# MCU_STM32H743BI.net
KiCad netlist of a schematic drawn in Altium Designer
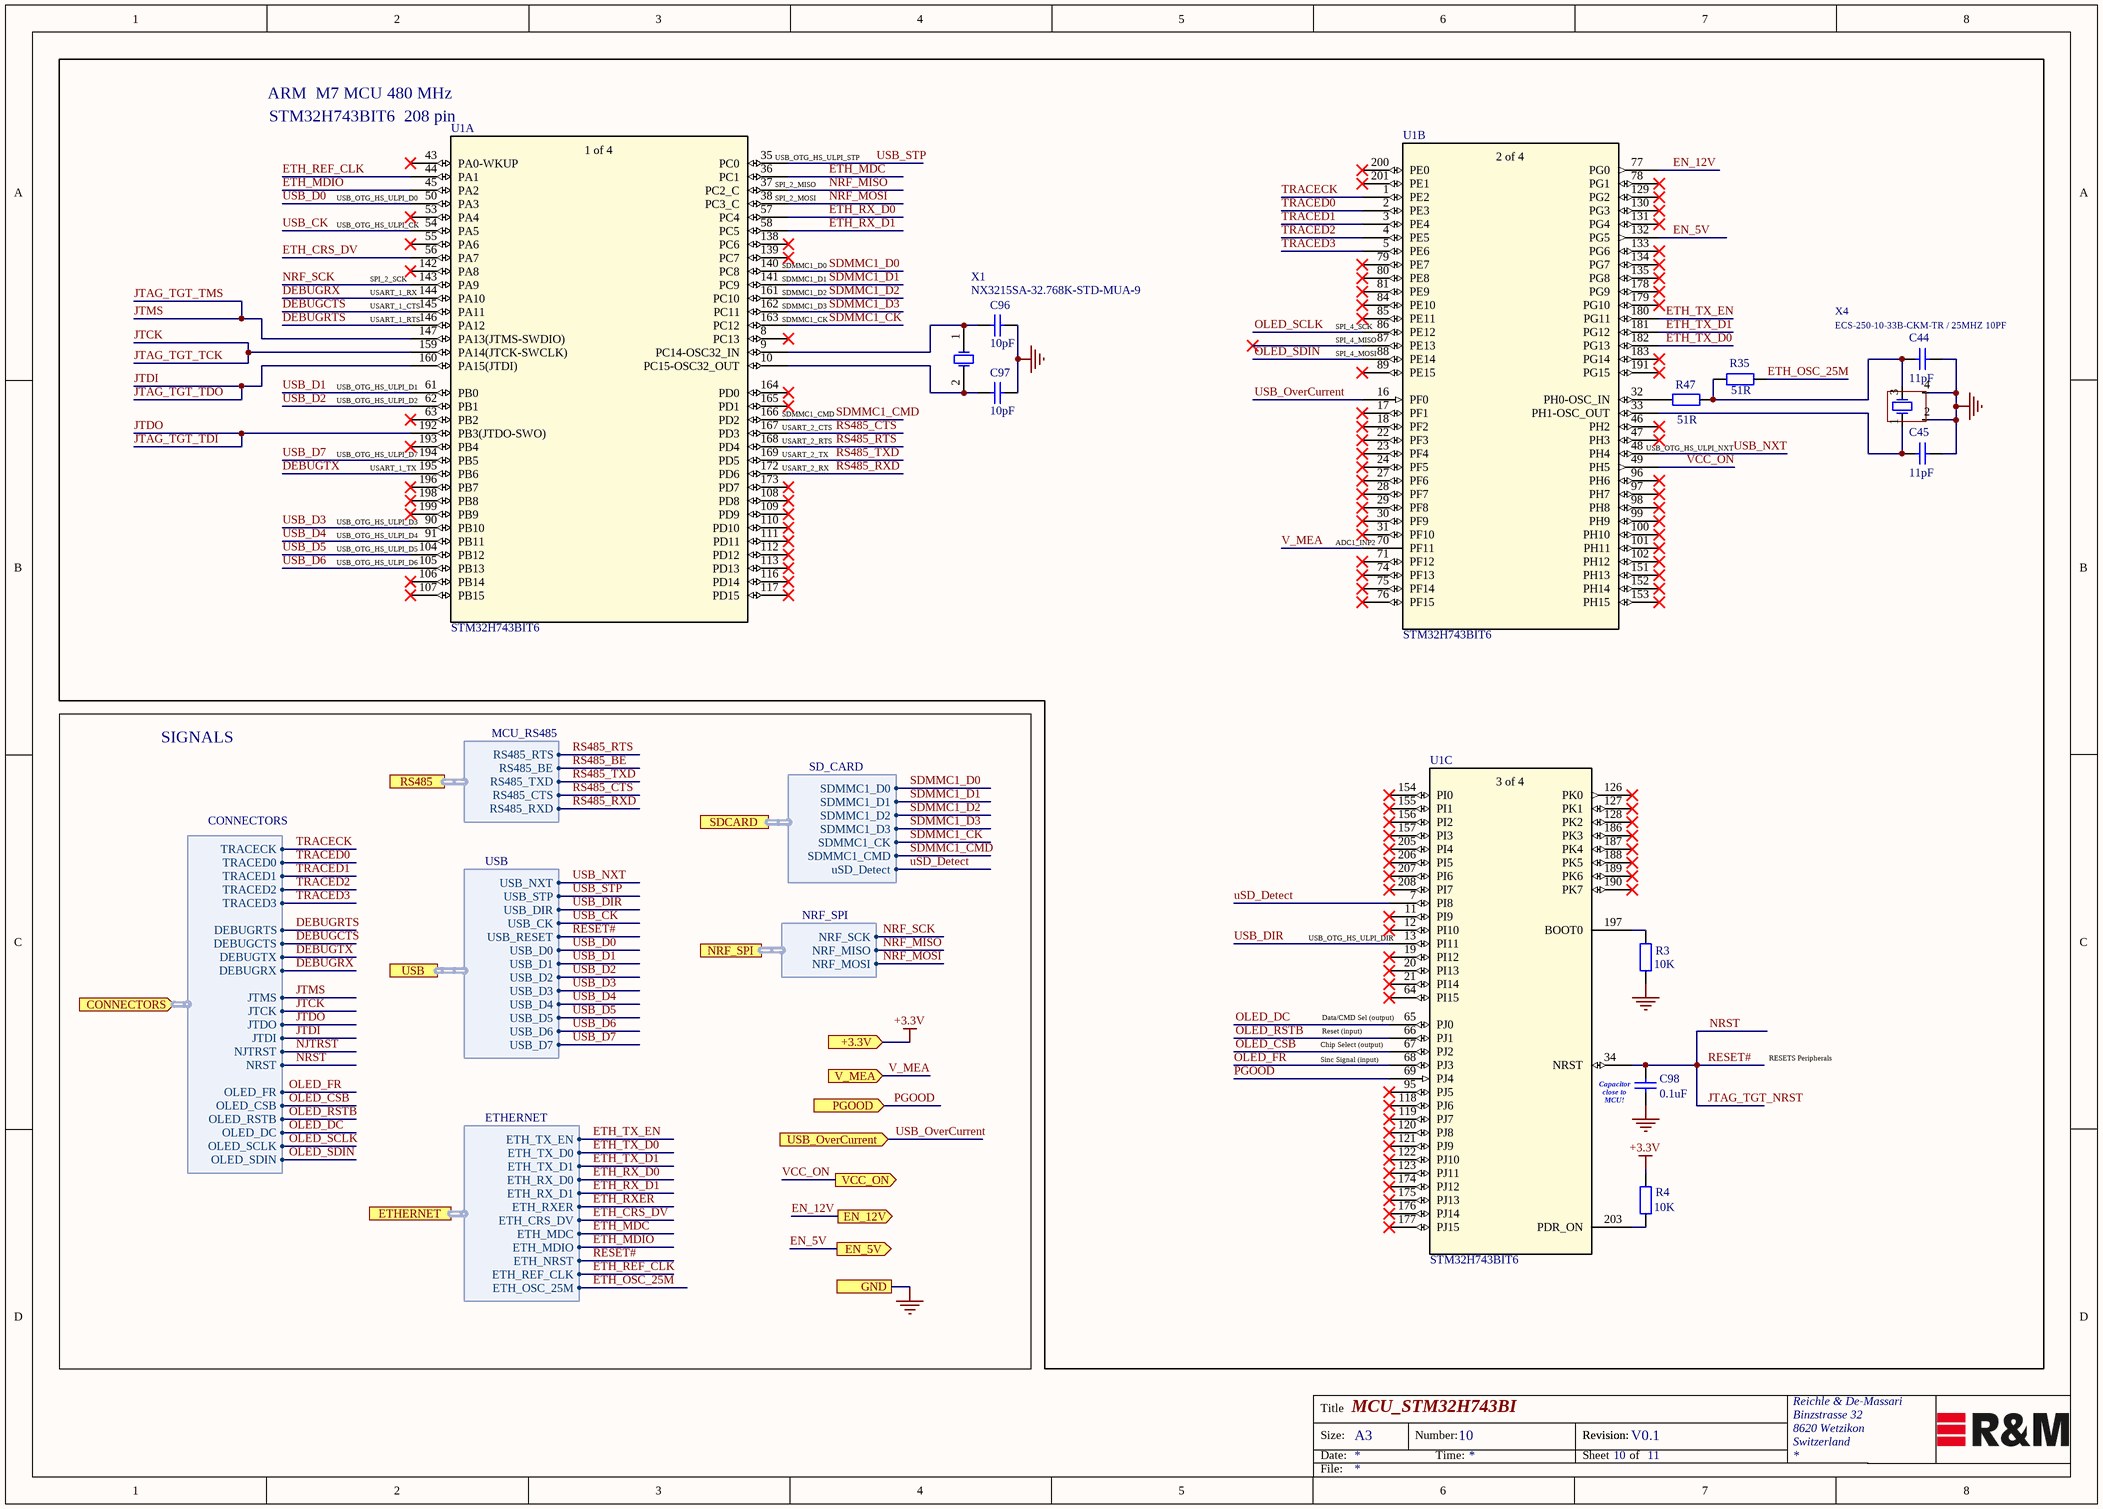
[diagram p0: MCU_STM32H743BI.SchDoc]

(export (version "E")
  (design (tool "Eeschema 10.0.6"))
  (components
    (comp (ref "C44")
      (value "11pF")
      (footprint "Ceramic Capacitor 0402 EIA")
      (description "11pF ±5% 50V Ceramic Capacitor C0G, NP0 0402 (1005 Metric)")
      (fields (field (name "TOLERANCE") "5%") (field (name "VOLTAGE") "50VDC"))
      (libsource (lib "RDM_ALT_SCH") (part "Cap_11pF_0402_50V"))
    )
    (comp (ref "C45")
      (value "11pF")
      (footprint "Ceramic Capacitor 0402 EIA")
      (description "11pF ±5% 50V Ceramic Capacitor C0G, NP0 0402 (1005 Metric)")
      (fields (field (name "TOLERANCE") "5%") (field (name "VOLTAGE") "50VDC"))
      (libsource (lib "RDM_ALT_SCH") (part "Cap_11pF_0402_50V"))
    )
    (comp (ref "C96")
      (value "10pF")
      (footprint "Ceramic Capacitor 0402 EIA")
      (description "10pF ±1% 50V Ceramic Capacitor C0G, NP0 0402 (1005 Metric)")
      (fields (field (name "TOLERANCE") "1%") (field (name "VOLTAGE") "50VDC"))
      (libsource (lib "RDM_ALT_SCH") (part "Cap_10pF_0402_50V"))
    )
    (comp (ref "C97")
      (value "10pF")
      (footprint "Ceramic Capacitor 0402 EIA")
      (description "10pF ±1% 50V Ceramic Capacitor C0G, NP0 0402 (1005 Metric)")
      (fields (field (name "TOLERANCE") "1%") (field (name "VOLTAGE") "50VDC"))
      (libsource (lib "RDM_ALT_SCH") (part "Cap_10pF_0402_50V"))
    )
    (comp (ref "C98")
      (value "0.1uF")
      (footprint "Ceramic Capacitor 0402 EIA")
      (description "0.1µF ±20% 10V Ceramic Capacitor X5R 0402 (1005 Metric)")
      (fields (field (name "TOLERANCE") "20%") (field (name "VOLTAGE") "10VDC"))
      (libsource (lib "RDM_ALT_SCH") (part "Cap_0.1uF_0402_10V"))
    )
    (comp (ref "R3")
      (value "10K")
      (footprint "Resistor 0402 EIA")
      (description "SMD 10K ohm 1% 50V General Purpose")
      (fields (field (name "TOLERANCE") "1%") (field (name "POWER") "63mW"))
      (libsource (lib "RDM_ALT_SCH") (part "Res_10K_0402"))
    )
    (comp (ref "R4")
      (value "10K")
      (footprint "Resistor 0402 EIA")
      (description "SMD 10K ohm 1% 50V General Purpose")
      (fields (field (name "TOLERANCE") "1%") (field (name "POWER") "63mW"))
      (libsource (lib "RDM_ALT_SCH") (part "Res_10K_0402"))
    )
    (comp (ref "R35")
      (value "51R")
      (footprint "Resistor 0402 EIA")
      (description "51 Ohms ±0.5% 0.063W, 1/16W Chip Resistor 0402 (1005 Metric) Thin Film")
      (fields (field (name "TOLERANCE") "±0.5%") (field (name "POWER") "62.5mW"))
      (libsource (lib "RDM_ALT_SCH") (part "Res_51R_0402_0.5%"))
    )
    (comp (ref "R47")
      (value "51R")
      (footprint "Resistor 0402 EIA")
      (description "51 Ohms ±0.5% 0.063W, 1/16W Chip Resistor 0402 (1005 Metric) Thin Film")
      (fields (field (name "TOLERANCE") "±0.5%") (field (name "POWER") "62.5mW"))
      (libsource (lib "RDM_ALT_SCH") (part "Res_51R_0402_0.5%"))
    )
    (comp (ref "U1")
      (value "STM32H743BIT6")
      (footprint "LQFP208_STM32H743BITx")
      (description "ARM Cortex-M7 STM32H7 Mikrocontroller IC 32-Bit 480MHz 2MB (2M x 8) FLASH 208-LQFP (28x28)")
      (fields (field (name "VOLTAGE") "1,62V-3.6V") (field (name "MANUFACTURER") "STMicroelectronics"))
      (libsource (lib "RDM_ALT_SCH") (part "STM32H7x3BIT"))
    )
    (comp (ref "X1")
      (value "NX3215SA-32.768K-STD-MUA-9")
      (footprint "NX3215SA")
      (description "32.768kHz ±20ppm Crystal 9pF 70 kOhms 2-SMD, No Lead")
      (fields (field (name "MANUFACTURER") "NDK America") (field (name "TOLERANCE") "±20ppm"))
      (libsource (lib "RDM_ALT_SCH") (part "CRYSTAL_2Pin_ NX3215SA-32.768K-STD-MUA-9"))
    )
    (comp (ref "X4")
      (value "ECS-250-10-33B-CKM-TR / 25MHZ 10PF")
      (footprint "ECS-33B")
      (description "25MHz ±10ppm Crystal 10pF 40 Ohms 4-SMD, No Lead")
      (fields (field (name "MANUFACTURER") "ESC Inc."))
      (libsource (lib "RDM_ALT_SCH") (part "CRYSTAL_4Pad_ECS-250-10-33B-CKM-TR"))
    )
  )
  (nets
    (net (code "7") (name "+3.3V") (class "Default")
      (node (ref "R4") (pin "1") (pinfunction "1_1") (pintype "passive"))
    )
    (net (code "9") (name "/DEBUGCTS") (class "Default")
      (node (ref "U1") (pin "145") (pinfunction "PA11_145") (pintype "bidirectional"))
    )
    (net (code "10") (name "/DEBUGRTS") (class "Default")
      (node (ref "U1") (pin "146") (pinfunction "PA12_146") (pintype "bidirectional"))
    )
    (net (code "11") (name "/DEBUGRX") (class "Default")
      (node (ref "U1") (pin "144") (pinfunction "PA10_144") (pintype "bidirectional"))
    )
    (net (code "12") (name "/DEBUGTX") (class "Default")
      (node (ref "U1") (pin "195") (pinfunction "PB6_195") (pintype "bidirectional"))
    )
    (net (code "13") (name "/EN_5V") (class "Default")
      (node (ref "U1") (pin "132") (pinfunction "PG5_132") (pintype "bidirectional"))
    )
    (net (code "14") (name "/EN_12V") (class "Default")
      (node (ref "U1") (pin "77") (pinfunction "PG0_77") (pintype "bidirectional"))
    )
    (net (code "15") (name "/ETH_CRS_DV") (class "Default")
      (node (ref "U1") (pin "56") (pinfunction "PA7_56") (pintype "bidirectional"))
    )
    (net (code "16") (name "/ETH_MDC") (class "Default")
      (node (ref "U1") (pin "36") (pinfunction "PC1_36") (pintype "bidirectional"))
    )
    (net (code "17") (name "/ETH_MDIO") (class "Default")
      (node (ref "U1") (pin "45") (pinfunction "PA2_45") (pintype "bidirectional"))
    )
    (net (code "18") (name "/ETH_OSC_25M") (class "Default")
      (node (ref "R35") (pin "2") (pinfunction "2_2") (pintype "passive"))
    )
    (net (code "19") (name "/ETH_REF_CLK") (class "Default")
      (node (ref "U1") (pin "44") (pinfunction "PA1_44") (pintype "bidirectional"))
    )
    (net (code "21") (name "/ETH_RX_D0") (class "Default")
      (node (ref "U1") (pin "57") (pinfunction "PC4_57") (pintype "bidirectional"))
    )
    (net (code "22") (name "/ETH_RX_D1") (class "Default")
      (node (ref "U1") (pin "58") (pinfunction "PC5_58") (pintype "bidirectional"))
    )
    (net (code "23") (name "/ETH_TX_D0") (class "Default")
      (node (ref "U1") (pin "182") (pinfunction "PG13_182") (pintype "bidirectional"))
    )
    (net (code "24") (name "/ETH_TX_D1") (class "Default")
      (node (ref "U1") (pin "181") (pinfunction "PG12_181") (pintype "bidirectional"))
    )
    (net (code "25") (name "/ETH_TX_EN") (class "Default")
      (node (ref "U1") (pin "180") (pinfunction "PG11_180") (pintype "bidirectional"))
    )
    (net (code "26") (name "/JTAG_TGT_NRST") (class "Default")
      (node (ref "C98") (pin "2") (pinfunction "2_2") (pintype "passive"))
      (node (ref "U1") (pin "34") (pinfunction "NRST_34") (pintype "bidirectional"))
    )
    (net (code "27") (name "/JTAG_TGT_TCK") (class "Default")
      (node (ref "U1") (pin "159") (pinfunction "PA14(JTCK-SWCLK)_159") (pintype "bidirectional"))
    )
    (net (code "28") (name "/JTAG_TGT_TDI") (class "Default")
      (node (ref "U1") (pin "192") (pinfunction "PB3(JTDO-SWO)_192") (pintype "bidirectional"))
    )
    (net (code "29") (name "/JTAG_TGT_TDO") (class "Default")
      (node (ref "U1") (pin "160") (pinfunction "PA15(JTDI)_160") (pintype "bidirectional"))
    )
    (net (code "30") (name "/JTAG_TGT_TMS") (class "Default")
      (node (ref "U1") (pin "147") (pinfunction "PA13(JTMS-SWDIO)_147") (pintype "bidirectional"))
    )
    (net (code "32") (name "/NRF_MISO") (class "Default")
      (node (ref "U1") (pin "37") (pinfunction "PC2_C_37") (pintype "bidirectional"))
    )
    (net (code "33") (name "/NRF_MOSI") (class "Default")
      (node (ref "U1") (pin "38") (pinfunction "PC3_C_38") (pintype "bidirectional"))
    )
    (net (code "34") (name "/NRF_SCK") (class "Default")
      (node (ref "U1") (pin "143") (pinfunction "PA9_143") (pintype "bidirectional"))
    )
    (net (code "35") (name "/OLED_CSB") (class "Default")
      (node (ref "U1") (pin "67") (pinfunction "PJ2_67") (pintype "bidirectional"))
    )
    (net (code "36") (name "/OLED_DC") (class "Default")
      (node (ref "U1") (pin "65") (pinfunction "PJ0_65") (pintype "bidirectional"))
    )
    (net (code "37") (name "/OLED_FR") (class "Default")
      (node (ref "U1") (pin "68") (pinfunction "PJ3_68") (pintype "bidirectional"))
    )
    (net (code "38") (name "/OLED_RSTB") (class "Default")
      (node (ref "U1") (pin "66") (pinfunction "PJ1_66") (pintype "bidirectional"))
    )
    (net (code "39") (name "/OLED_SCLK") (class "Default")
      (node (ref "U1") (pin "86") (pinfunction "PE12_86") (pintype "bidirectional"))
    )
    (net (code "40") (name "/OLED_SDIN") (class "Default")
      (node (ref "U1") (pin "88") (pinfunction "PE14_88") (pintype "bidirectional"))
    )
    (net (code "41") (name "/PGOOD") (class "Default")
      (node (ref "U1") (pin "69") (pinfunction "PJ4_69") (pintype "bidirectional"))
    )
    (net (code "43") (name "/RS485_CTS") (class "Default")
      (node (ref "U1") (pin "167") (pinfunction "PD3_167") (pintype "bidirectional"))
    )
    (net (code "44") (name "/RS485_RTS") (class "Default")
      (node (ref "U1") (pin "168") (pinfunction "PD4_168") (pintype "bidirectional"))
    )
    (net (code "45") (name "/RS485_RXD") (class "Default")
      (node (ref "U1") (pin "172") (pinfunction "PD6_172") (pintype "bidirectional"))
    )
    (net (code "46") (name "/RS485_TXD") (class "Default")
      (node (ref "U1") (pin "169") (pinfunction "PD5_169") (pintype "bidirectional"))
    )
    (net (code "47") (name "/SDMMC1_CK") (class "Default")
      (node (ref "U1") (pin "163") (pinfunction "PC12_163") (pintype "bidirectional"))
    )
    (net (code "48") (name "/SDMMC1_CMD") (class "Default")
      (node (ref "U1") (pin "166") (pinfunction "PD2_166") (pintype "bidirectional"))
    )
    (net (code "49") (name "/SDMMC1_D0") (class "Default")
      (node (ref "U1") (pin "140") (pinfunction "PC8_140") (pintype "bidirectional"))
    )
    (net (code "50") (name "/SDMMC1_D1") (class "Default")
      (node (ref "U1") (pin "141") (pinfunction "PC9_141") (pintype "bidirectional"))
    )
    (net (code "51") (name "/SDMMC1_D2") (class "Default")
      (node (ref "U1") (pin "161") (pinfunction "PC10_161") (pintype "bidirectional"))
    )
    (net (code "52") (name "/SDMMC1_D3") (class "Default")
      (node (ref "U1") (pin "162") (pinfunction "PC11_162") (pintype "bidirectional"))
    )
    (net (code "53") (name "/TRACECK") (class "Default")
      (node (ref "U1") (pin "1") (pinfunction "PE2_1") (pintype "bidirectional"))
    )
    (net (code "54") (name "/TRACED0") (class "Default")
      (node (ref "U1") (pin "2") (pinfunction "PE3_2") (pintype "bidirectional"))
    )
    (net (code "55") (name "/TRACED1") (class "Default")
      (node (ref "U1") (pin "3") (pinfunction "PE4_3") (pintype "bidirectional"))
    )
    (net (code "56") (name "/TRACED2") (class "Default")
      (node (ref "U1") (pin "4") (pinfunction "PE5_4") (pintype "bidirectional"))
    )
    (net (code "57") (name "/TRACED3") (class "Default")
      (node (ref "U1") (pin "5") (pinfunction "PE6_5") (pintype "bidirectional"))
    )
    (net (code "58") (name "/USB_CK") (class "Default")
      (node (ref "U1") (pin "54") (pinfunction "PA5_54") (pintype "bidirectional"))
    )
    (net (code "59") (name "/USB_D0") (class "Default")
      (node (ref "U1") (pin "50") (pinfunction "PA3_50") (pintype "bidirectional"))
    )
    (net (code "60") (name "/USB_D1") (class "Default")
      (node (ref "U1") (pin "61") (pinfunction "PB0_61") (pintype "bidirectional"))
    )
    (net (code "61") (name "/USB_D2") (class "Default")
      (node (ref "U1") (pin "62") (pinfunction "PB1_62") (pintype "bidirectional"))
    )
    (net (code "62") (name "/USB_D3") (class "Default")
      (node (ref "U1") (pin "90") (pinfunction "PB10_90") (pintype "bidirectional"))
    )
    (net (code "63") (name "/USB_D4") (class "Default")
      (node (ref "U1") (pin "91") (pinfunction "PB11_91") (pintype "bidirectional"))
    )
    (net (code "64") (name "/USB_D5") (class "Default")
      (node (ref "U1") (pin "104") (pinfunction "PB12_104") (pintype "bidirectional"))
    )
    (net (code "65") (name "/USB_D6") (class "Default")
      (node (ref "U1") (pin "105") (pinfunction "PB13_105") (pintype "bidirectional"))
    )
    (net (code "66") (name "/USB_D7") (class "Default")
      (node (ref "U1") (pin "194") (pinfunction "PB5_194") (pintype "bidirectional"))
    )
    (net (code "67") (name "/USB_DIR") (class "Default")
      (node (ref "U1") (pin "13") (pinfunction "PI11_13") (pintype "bidirectional"))
    )
    (net (code "68") (name "/USB_NXT") (class "Default")
      (node (ref "U1") (pin "48") (pinfunction "PH4_48") (pintype "bidirectional"))
    )
    (net (code "69") (name "/USB_OverCurrent") (class "Default")
      (node (ref "U1") (pin "16") (pinfunction "PF0_16") (pintype "bidirectional"))
    )
    (net (code "70") (name "/USB_STP") (class "Default")
      (node (ref "U1") (pin "35") (pinfunction "PC0_35") (pintype "bidirectional"))
    )
    (net (code "71") (name "/VCC_ON") (class "Default")
      (node (ref "U1") (pin "49") (pinfunction "PH5_49") (pintype "bidirectional"))
    )
    (net (code "72") (name "/V_MEA") (class "Default")
      (node (ref "U1") (pin "70") (pinfunction "PF11_70") (pintype "bidirectional"))
    )
    (net (code "73") (name "/uSD_Detect") (class "Default")
      (node (ref "U1") (pin "7") (pinfunction "PI8_7") (pintype "bidirectional"))
    )
    (net (code "80") (name "GND") (class "Default")
      (node (ref "C44") (pin "1") (pinfunction "1_1") (pintype "passive"))
      (node (ref "C45") (pin "1") (pinfunction "1_1") (pintype "passive"))
      (node (ref "C96") (pin "1") (pinfunction "1_1") (pintype "passive"))
      (node (ref "C97") (pin "1") (pinfunction "1_1") (pintype "passive"))
      (node (ref "C98") (pin "1") (pinfunction "1_1") (pintype "passive"))
      (node (ref "R3") (pin "2") (pinfunction "2_2") (pintype "passive"))
      (node (ref "X4") (pin "2") (pinfunction "OSC2_2") (pintype "passive"))
      (node (ref "X4") (pin "4") (pinfunction "OSC3_4") (pintype "passive"))
    )
    (net (code "81") (name "Net-(C44-Pad2)") (class "Default")
      (node (ref "C44") (pin "2") (pinfunction "2_2") (pintype "passive"))
      (node (ref "R35") (pin "1") (pinfunction "1_1") (pintype "passive"))
      (node (ref "R47") (pin "2") (pinfunction "2_2") (pintype "passive"))
      (node (ref "X4") (pin "3") (pinfunction "OSC2_3") (pintype "passive"))
    )
    (net (code "82") (name "Net-(U1A-PC14-OSC32_IN)") (class "Default")
      (node (ref "C96") (pin "2") (pinfunction "2_2") (pintype "passive"))
      (node (ref "U1") (pin "9") (pinfunction "PC14-OSC32_IN_9") (pintype "bidirectional"))
      (node (ref "X1") (pin "1") (pinfunction "OSC1_1") (pintype "passive"))
    )
    (net (code "83") (name "Net-(U1A-PC15-OSC32_OUT)") (class "Default")
      (node (ref "C97") (pin "2") (pinfunction "2_2") (pintype "passive"))
      (node (ref "U1") (pin "10") (pinfunction "PC15-OSC32_OUT_10") (pintype "bidirectional"))
      (node (ref "X1") (pin "2") (pinfunction "OSC2_2") (pintype "passive"))
    )
    (net (code "84") (name "Net-(U1B-PH0-OSC_IN)") (class "Default")
      (node (ref "R47") (pin "1") (pinfunction "1_1") (pintype "passive"))
      (node (ref "U1") (pin "32") (pinfunction "PH0-OSC_IN_32") (pintype "bidirectional"))
    )
    (net (code "85") (name "Net-(U1B-PH1-OSC_OUT)") (class "Default")
      (node (ref "C45") (pin "2") (pinfunction "2_2") (pintype "passive"))
      (node (ref "U1") (pin "33") (pinfunction "PH1-OSC_OUT_33") (pintype "bidirectional"))
      (node (ref "X4") (pin "1") (pinfunction "OSC1_1") (pintype "passive"))
    )
    (net (code "86") (name "Net-(U1C-BOOT0)") (class "Default")
      (node (ref "R3") (pin "1") (pinfunction "1_1") (pintype "passive"))
      (node (ref "U1") (pin "197") (pinfunction "BOOT0_197") (pintype "input"))
    )
    (net (code "87") (name "Net-(U1C-PDR_ON)") (class "Default")
      (node (ref "R4") (pin "2") (pinfunction "2_2") (pintype "passive"))
      (node (ref "U1") (pin "203") (pinfunction "PDR_ON_203") (pintype "passive"))
    )
    (net (code "88") (name "unconnected-(U1A-PA0-WKUP-Pad43)") (class "Default")
      (node (ref "U1") (pin "43") (pinfunction "PA0-WKUP_43") (pintype "bidirectional+no_connect"))
    )
    (net (code "89") (name "unconnected-(U1A-PA4-Pad53)") (class "Default")
      (node (ref "U1") (pin "53") (pinfunction "PA4_53") (pintype "bidirectional+no_connect"))
    )
    (net (code "90") (name "unconnected-(U1A-PA6-Pad55)") (class "Default")
      (node (ref "U1") (pin "55") (pinfunction "PA6_55") (pintype "bidirectional+no_connect"))
    )
    (net (code "91") (name "unconnected-(U1A-PA8-Pad142)") (class "Default")
      (node (ref "U1") (pin "142") (pinfunction "PA8_142") (pintype "bidirectional+no_connect"))
    )
    (net (code "92") (name "unconnected-(U1A-PB2-Pad63)") (class "Default")
      (node (ref "U1") (pin "63") (pinfunction "PB2_63") (pintype "bidirectional+no_connect"))
    )
    (net (code "93") (name "unconnected-(U1A-PB4-Pad193)") (class "Default")
      (node (ref "U1") (pin "193") (pinfunction "PB4_193") (pintype "bidirectional+no_connect"))
    )
    (net (code "94") (name "unconnected-(U1A-PB7-Pad196)") (class "Default")
      (node (ref "U1") (pin "196") (pinfunction "PB7_196") (pintype "bidirectional+no_connect"))
    )
    (net (code "95") (name "unconnected-(U1A-PB8-Pad198)") (class "Default")
      (node (ref "U1") (pin "198") (pinfunction "PB8_198") (pintype "bidirectional+no_connect"))
    )
    (net (code "96") (name "unconnected-(U1A-PB9-Pad199)") (class "Default")
      (node (ref "U1") (pin "199") (pinfunction "PB9_199") (pintype "bidirectional+no_connect"))
    )
    (net (code "97") (name "unconnected-(U1A-PB14-Pad106)") (class "Default")
      (node (ref "U1") (pin "106") (pinfunction "PB14_106") (pintype "bidirectional+no_connect"))
    )
    (net (code "98") (name "unconnected-(U1A-PB15-Pad107)") (class "Default")
      (node (ref "U1") (pin "107") (pinfunction "PB15_107") (pintype "bidirectional+no_connect"))
    )
    (net (code "99") (name "unconnected-(U1A-PC6-Pad138)") (class "Default")
      (node (ref "U1") (pin "138") (pinfunction "PC6_138") (pintype "bidirectional+no_connect"))
    )
    (net (code "100") (name "unconnected-(U1A-PC7-Pad139)") (class "Default")
      (node (ref "U1") (pin "139") (pinfunction "PC7_139") (pintype "bidirectional+no_connect"))
    )
    (net (code "101") (name "unconnected-(U1A-PC13-Pad8)") (class "Default")
      (node (ref "U1") (pin "8") (pinfunction "PC13_8") (pintype "bidirectional+no_connect"))
    )
    (net (code "102") (name "unconnected-(U1A-PD0-Pad164)") (class "Default")
      (node (ref "U1") (pin "164") (pinfunction "PD0_164") (pintype "bidirectional+no_connect"))
    )
    (net (code "103") (name "unconnected-(U1A-PD1-Pad165)") (class "Default")
      (node (ref "U1") (pin "165") (pinfunction "PD1_165") (pintype "bidirectional+no_connect"))
    )
    (net (code "104") (name "unconnected-(U1A-PD7-Pad173)") (class "Default")
      (node (ref "U1") (pin "173") (pinfunction "PD7_173") (pintype "bidirectional+no_connect"))
    )
    (net (code "105") (name "unconnected-(U1A-PD8-Pad108)") (class "Default")
      (node (ref "U1") (pin "108") (pinfunction "PD8_108") (pintype "bidirectional+no_connect"))
    )
    (net (code "106") (name "unconnected-(U1A-PD9-Pad109)") (class "Default")
      (node (ref "U1") (pin "109") (pinfunction "PD9_109") (pintype "bidirectional+no_connect"))
    )
    (net (code "107") (name "unconnected-(U1A-PD10-Pad110)") (class "Default")
      (node (ref "U1") (pin "110") (pinfunction "PD10_110") (pintype "bidirectional+no_connect"))
    )
    (net (code "108") (name "unconnected-(U1A-PD11-Pad111)") (class "Default")
      (node (ref "U1") (pin "111") (pinfunction "PD11_111") (pintype "bidirectional+no_connect"))
    )
    (net (code "109") (name "unconnected-(U1A-PD12-Pad112)") (class "Default")
      (node (ref "U1") (pin "112") (pinfunction "PD12_112") (pintype "bidirectional+no_connect"))
    )
    (net (code "110") (name "unconnected-(U1A-PD13-Pad113)") (class "Default")
      (node (ref "U1") (pin "113") (pinfunction "PD13_113") (pintype "bidirectional+no_connect"))
    )
    (net (code "111") (name "unconnected-(U1A-PD14-Pad116)") (class "Default")
      (node (ref "U1") (pin "116") (pinfunction "PD14_116") (pintype "bidirectional+no_connect"))
    )
    (net (code "112") (name "unconnected-(U1A-PD15-Pad117)") (class "Default")
      (node (ref "U1") (pin "117") (pinfunction "PD15_117") (pintype "bidirectional+no_connect"))
    )
    (net (code "113") (name "unconnected-(U1B-PE0-Pad200)") (class "Default")
      (node (ref "U1") (pin "200") (pinfunction "PE0_200") (pintype "bidirectional+no_connect"))
    )
    (net (code "114") (name "unconnected-(U1B-PE1-Pad201)") (class "Default")
      (node (ref "U1") (pin "201") (pinfunction "PE1_201") (pintype "bidirectional+no_connect"))
    )
    (net (code "115") (name "unconnected-(U1B-PE7-Pad79)") (class "Default")
      (node (ref "U1") (pin "79") (pinfunction "PE7_79") (pintype "bidirectional+no_connect"))
    )
    (net (code "116") (name "unconnected-(U1B-PE8-Pad80)") (class "Default")
      (node (ref "U1") (pin "80") (pinfunction "PE8_80") (pintype "bidirectional+no_connect"))
    )
    (net (code "117") (name "unconnected-(U1B-PE9-Pad81)") (class "Default")
      (node (ref "U1") (pin "81") (pinfunction "PE9_81") (pintype "bidirectional+no_connect"))
    )
    (net (code "118") (name "unconnected-(U1B-PE10-Pad84)") (class "Default")
      (node (ref "U1") (pin "84") (pinfunction "PE10_84") (pintype "bidirectional+no_connect"))
    )
    (net (code "119") (name "unconnected-(U1B-PE11-Pad85)") (class "Default")
      (node (ref "U1") (pin "85") (pinfunction "PE11_85") (pintype "bidirectional+no_connect"))
    )
    (net (code "120") (name "unconnected-(U1B-PE13-Pad87)") (class "Default")
      (node (ref "U1") (pin "87") (pinfunction "PE13_87") (pintype "bidirectional+no_connect"))
    )
    (net (code "121") (name "unconnected-(U1B-PE15-Pad89)") (class "Default")
      (node (ref "U1") (pin "89") (pinfunction "PE15_89") (pintype "bidirectional+no_connect"))
    )
    (net (code "122") (name "unconnected-(U1B-PF1-Pad17)") (class "Default")
      (node (ref "U1") (pin "17") (pinfunction "PF1_17") (pintype "bidirectional+no_connect"))
    )
    (net (code "123") (name "unconnected-(U1B-PF2-Pad18)") (class "Default")
      (node (ref "U1") (pin "18") (pinfunction "PF2_18") (pintype "bidirectional+no_connect"))
    )
    (net (code "124") (name "unconnected-(U1B-PF3-Pad22)") (class "Default")
      (node (ref "U1") (pin "22") (pinfunction "PF3_22") (pintype "bidirectional+no_connect"))
    )
    (net (code "125") (name "unconnected-(U1B-PF4-Pad23)") (class "Default")
      (node (ref "U1") (pin "23") (pinfunction "PF4_23") (pintype "bidirectional+no_connect"))
    )
    (net (code "126") (name "unconnected-(U1B-PF5-Pad24)") (class "Default")
      (node (ref "U1") (pin "24") (pinfunction "PF5_24") (pintype "bidirectional+no_connect"))
    )
    (net (code "127") (name "unconnected-(U1B-PF6-Pad27)") (class "Default")
      (node (ref "U1") (pin "27") (pinfunction "PF6_27") (pintype "bidirectional+no_connect"))
    )
    (net (code "128") (name "unconnected-(U1B-PF7-Pad28)") (class "Default")
      (node (ref "U1") (pin "28") (pinfunction "PF7_28") (pintype "bidirectional+no_connect"))
    )
    (net (code "129") (name "unconnected-(U1B-PF8-Pad29)") (class "Default")
      (node (ref "U1") (pin "29") (pinfunction "PF8_29") (pintype "bidirectional+no_connect"))
    )
    (net (code "130") (name "unconnected-(U1B-PF9-Pad30)") (class "Default")
      (node (ref "U1") (pin "30") (pinfunction "PF9_30") (pintype "bidirectional+no_connect"))
    )
    (net (code "131") (name "unconnected-(U1B-PF10-Pad31)") (class "Default")
      (node (ref "U1") (pin "31") (pinfunction "PF10_31") (pintype "bidirectional+no_connect"))
    )
    (net (code "132") (name "unconnected-(U1B-PF12-Pad71)") (class "Default")
      (node (ref "U1") (pin "71") (pinfunction "PF12_71") (pintype "bidirectional+no_connect"))
    )
    (net (code "133") (name "unconnected-(U1B-PF13-Pad74)") (class "Default")
      (node (ref "U1") (pin "74") (pinfunction "PF13_74") (pintype "bidirectional+no_connect"))
    )
    (net (code "134") (name "unconnected-(U1B-PF14-Pad75)") (class "Default")
      (node (ref "U1") (pin "75") (pinfunction "PF14_75") (pintype "bidirectional+no_connect"))
    )
    (net (code "135") (name "unconnected-(U1B-PF15-Pad76)") (class "Default")
      (node (ref "U1") (pin "76") (pinfunction "PF15_76") (pintype "bidirectional+no_connect"))
    )
    (net (code "136") (name "unconnected-(U1B-PG1-Pad78)") (class "Default")
      (node (ref "U1") (pin "78") (pinfunction "PG1_78") (pintype "bidirectional+no_connect"))
    )
    (net (code "137") (name "unconnected-(U1B-PG2-Pad129)") (class "Default")
      (node (ref "U1") (pin "129") (pinfunction "PG2_129") (pintype "bidirectional+no_connect"))
    )
    (net (code "138") (name "unconnected-(U1B-PG3-Pad130)") (class "Default")
      (node (ref "U1") (pin "130") (pinfunction "PG3_130") (pintype "bidirectional+no_connect"))
    )
    (net (code "139") (name "unconnected-(U1B-PG4-Pad131)") (class "Default")
      (node (ref "U1") (pin "131") (pinfunction "PG4_131") (pintype "bidirectional+no_connect"))
    )
    (net (code "140") (name "unconnected-(U1B-PG6-Pad133)") (class "Default")
      (node (ref "U1") (pin "133") (pinfunction "PG6_133") (pintype "bidirectional+no_connect"))
    )
    (net (code "141") (name "unconnected-(U1B-PG7-Pad134)") (class "Default")
      (node (ref "U1") (pin "134") (pinfunction "PG7_134") (pintype "bidirectional+no_connect"))
    )
    (net (code "142") (name "unconnected-(U1B-PG8-Pad135)") (class "Default")
      (node (ref "U1") (pin "135") (pinfunction "PG8_135") (pintype "bidirectional+no_connect"))
    )
    (net (code "143") (name "unconnected-(U1B-PG9-Pad178)") (class "Default")
      (node (ref "U1") (pin "178") (pinfunction "PG9_178") (pintype "bidirectional+no_connect"))
    )
    (net (code "144") (name "unconnected-(U1B-PG10-Pad179)") (class "Default")
      (node (ref "U1") (pin "179") (pinfunction "PG10_179") (pintype "bidirectional+no_connect"))
    )
    (net (code "145") (name "unconnected-(U1B-PG14-Pad183)") (class "Default")
      (node (ref "U1") (pin "183") (pinfunction "PG14_183") (pintype "bidirectional+no_connect"))
    )
    (net (code "146") (name "unconnected-(U1B-PG15-Pad191)") (class "Default")
      (node (ref "U1") (pin "191") (pinfunction "PG15_191") (pintype "bidirectional+no_connect"))
    )
    (net (code "147") (name "unconnected-(U1B-PH2-Pad46)") (class "Default")
      (node (ref "U1") (pin "46") (pinfunction "PH2_46") (pintype "bidirectional+no_connect"))
    )
    (net (code "148") (name "unconnected-(U1B-PH3-Pad47)") (class "Default")
      (node (ref "U1") (pin "47") (pinfunction "PH3_47") (pintype "bidirectional+no_connect"))
    )
    (net (code "149") (name "unconnected-(U1B-PH6-Pad96)") (class "Default")
      (node (ref "U1") (pin "96") (pinfunction "PH6_96") (pintype "bidirectional+no_connect"))
    )
    (net (code "150") (name "unconnected-(U1B-PH7-Pad97)") (class "Default")
      (node (ref "U1") (pin "97") (pinfunction "PH7_97") (pintype "bidirectional+no_connect"))
    )
    (net (code "151") (name "unconnected-(U1B-PH8-Pad98)") (class "Default")
      (node (ref "U1") (pin "98") (pinfunction "PH8_98") (pintype "bidirectional+no_connect"))
    )
    (net (code "152") (name "unconnected-(U1B-PH9-Pad99)") (class "Default")
      (node (ref "U1") (pin "99") (pinfunction "PH9_99") (pintype "bidirectional+no_connect"))
    )
    (net (code "153") (name "unconnected-(U1B-PH10-Pad100)") (class "Default")
      (node (ref "U1") (pin "100") (pinfunction "PH10_100") (pintype "bidirectional+no_connect"))
    )
    (net (code "154") (name "unconnected-(U1B-PH11-Pad101)") (class "Default")
      (node (ref "U1") (pin "101") (pinfunction "PH11_101") (pintype "bidirectional+no_connect"))
    )
    (net (code "155") (name "unconnected-(U1B-PH12-Pad102)") (class "Default")
      (node (ref "U1") (pin "102") (pinfunction "PH12_102") (pintype "bidirectional+no_connect"))
    )
    (net (code "156") (name "unconnected-(U1B-PH13-Pad151)") (class "Default")
      (node (ref "U1") (pin "151") (pinfunction "PH13_151") (pintype "bidirectional+no_connect"))
    )
    (net (code "157") (name "unconnected-(U1B-PH14-Pad152)") (class "Default")
      (node (ref "U1") (pin "152") (pinfunction "PH14_152") (pintype "bidirectional+no_connect"))
    )
    (net (code "158") (name "unconnected-(U1B-PH15-Pad153)") (class "Default")
      (node (ref "U1") (pin "153") (pinfunction "PH15_153") (pintype "bidirectional+no_connect"))
    )
    (net (code "159") (name "unconnected-(U1C-PI0-Pad154)") (class "Default")
      (node (ref "U1") (pin "154") (pinfunction "PI0_154") (pintype "bidirectional+no_connect"))
    )
    (net (code "160") (name "unconnected-(U1C-PI1-Pad155)") (class "Default")
      (node (ref "U1") (pin "155") (pinfunction "PI1_155") (pintype "bidirectional+no_connect"))
    )
    (net (code "161") (name "unconnected-(U1C-PI2-Pad156)") (class "Default")
      (node (ref "U1") (pin "156") (pinfunction "PI2_156") (pintype "bidirectional+no_connect"))
    )
    (net (code "162") (name "unconnected-(U1C-PI3-Pad157)") (class "Default")
      (node (ref "U1") (pin "157") (pinfunction "PI3_157") (pintype "bidirectional+no_connect"))
    )
    (net (code "163") (name "unconnected-(U1C-PI4-Pad205)") (class "Default")
      (node (ref "U1") (pin "205") (pinfunction "PI4_205") (pintype "bidirectional+no_connect"))
    )
    (net (code "164") (name "unconnected-(U1C-PI5-Pad206)") (class "Default")
      (node (ref "U1") (pin "206") (pinfunction "PI5_206") (pintype "bidirectional+no_connect"))
    )
    (net (code "165") (name "unconnected-(U1C-PI6-Pad207)") (class "Default")
      (node (ref "U1") (pin "207") (pinfunction "PI6_207") (pintype "bidirectional+no_connect"))
    )
    (net (code "166") (name "unconnected-(U1C-PI7-Pad208)") (class "Default")
      (node (ref "U1") (pin "208") (pinfunction "PI7_208") (pintype "bidirectional+no_connect"))
    )
    (net (code "167") (name "unconnected-(U1C-PI9-Pad11)") (class "Default")
      (node (ref "U1") (pin "11") (pinfunction "PI9_11") (pintype "bidirectional+no_connect"))
    )
    (net (code "168") (name "unconnected-(U1C-PI10-Pad12)") (class "Default")
      (node (ref "U1") (pin "12") (pinfunction "PI10_12") (pintype "bidirectional+no_connect"))
    )
    (net (code "169") (name "unconnected-(U1C-PI12-Pad19)") (class "Default")
      (node (ref "U1") (pin "19") (pinfunction "PI12_19") (pintype "bidirectional+no_connect"))
    )
    (net (code "170") (name "unconnected-(U1C-PI13-Pad20)") (class "Default")
      (node (ref "U1") (pin "20") (pinfunction "PI13_20") (pintype "bidirectional+no_connect"))
    )
    (net (code "171") (name "unconnected-(U1C-PI14-Pad21)") (class "Default")
      (node (ref "U1") (pin "21") (pinfunction "PI14_21") (pintype "bidirectional+no_connect"))
    )
    (net (code "172") (name "unconnected-(U1C-PI15-Pad64)") (class "Default")
      (node (ref "U1") (pin "64") (pinfunction "PI15_64") (pintype "bidirectional+no_connect"))
    )
    (net (code "173") (name "unconnected-(U1C-PJ5-Pad95)") (class "Default")
      (node (ref "U1") (pin "95") (pinfunction "PJ5_95") (pintype "bidirectional+no_connect"))
    )
    (net (code "174") (name "unconnected-(U1C-PJ6-Pad118)") (class "Default")
      (node (ref "U1") (pin "118") (pinfunction "PJ6_118") (pintype "bidirectional+no_connect"))
    )
    (net (code "175") (name "unconnected-(U1C-PJ7-Pad119)") (class "Default")
      (node (ref "U1") (pin "119") (pinfunction "PJ7_119") (pintype "bidirectional+no_connect"))
    )
    (net (code "176") (name "unconnected-(U1C-PJ8-Pad120)") (class "Default")
      (node (ref "U1") (pin "120") (pinfunction "PJ8_120") (pintype "bidirectional+no_connect"))
    )
    (net (code "177") (name "unconnected-(U1C-PJ9-Pad121)") (class "Default")
      (node (ref "U1") (pin "121") (pinfunction "PJ9_121") (pintype "bidirectional+no_connect"))
    )
    (net (code "178") (name "unconnected-(U1C-PJ10-Pad122)") (class "Default")
      (node (ref "U1") (pin "122") (pinfunction "PJ10_122") (pintype "bidirectional+no_connect"))
    )
    (net (code "179") (name "unconnected-(U1C-PJ11-Pad123)") (class "Default")
      (node (ref "U1") (pin "123") (pinfunction "PJ11_123") (pintype "bidirectional+no_connect"))
    )
    (net (code "180") (name "unconnected-(U1C-PJ12-Pad174)") (class "Default")
      (node (ref "U1") (pin "174") (pinfunction "PJ12_174") (pintype "bidirectional+no_connect"))
    )
    (net (code "181") (name "unconnected-(U1C-PJ13-Pad175)") (class "Default")
      (node (ref "U1") (pin "175") (pinfunction "PJ13_175") (pintype "bidirectional+no_connect"))
    )
    (net (code "182") (name "unconnected-(U1C-PJ14-Pad176)") (class "Default")
      (node (ref "U1") (pin "176") (pinfunction "PJ14_176") (pintype "bidirectional+no_connect"))
    )
    (net (code "183") (name "unconnected-(U1C-PJ15-Pad177)") (class "Default")
      (node (ref "U1") (pin "177") (pinfunction "PJ15_177") (pintype "bidirectional+no_connect"))
    )
    (net (code "184") (name "unconnected-(U1C-PK0-Pad126)") (class "Default")
      (node (ref "U1") (pin "126") (pinfunction "PK0_126") (pintype "bidirectional+no_connect"))
    )
    (net (code "185") (name "unconnected-(U1C-PK1-Pad127)") (class "Default")
      (node (ref "U1") (pin "127") (pinfunction "PK1_127") (pintype "bidirectional+no_connect"))
    )
    (net (code "186") (name "unconnected-(U1C-PK2-Pad128)") (class "Default")
      (node (ref "U1") (pin "128") (pinfunction "PK2_128") (pintype "bidirectional+no_connect"))
    )
    (net (code "187") (name "unconnected-(U1C-PK3-Pad186)") (class "Default")
      (node (ref "U1") (pin "186") (pinfunction "PK3_186") (pintype "bidirectional+no_connect"))
    )
    (net (code "188") (name "unconnected-(U1C-PK4-Pad187)") (class "Default")
      (node (ref "U1") (pin "187") (pinfunction "PK4_187") (pintype "bidirectional+no_connect"))
    )
    (net (code "189") (name "unconnected-(U1C-PK5-Pad188)") (class "Default")
      (node (ref "U1") (pin "188") (pinfunction "PK5_188") (pintype "bidirectional+no_connect"))
    )
    (net (code "190") (name "unconnected-(U1C-PK6-Pad189)") (class "Default")
      (node (ref "U1") (pin "189") (pinfunction "PK6_189") (pintype "bidirectional+no_connect"))
    )
    (net (code "191") (name "unconnected-(U1C-PK7-Pad190)") (class "Default")
      (node (ref "U1") (pin "190") (pinfunction "PK7_190") (pintype "bidirectional+no_connect"))
    )
  )
)
